# Coil_Switching_System.net
KiCad netlist of a schematic drawn in Altium Designer
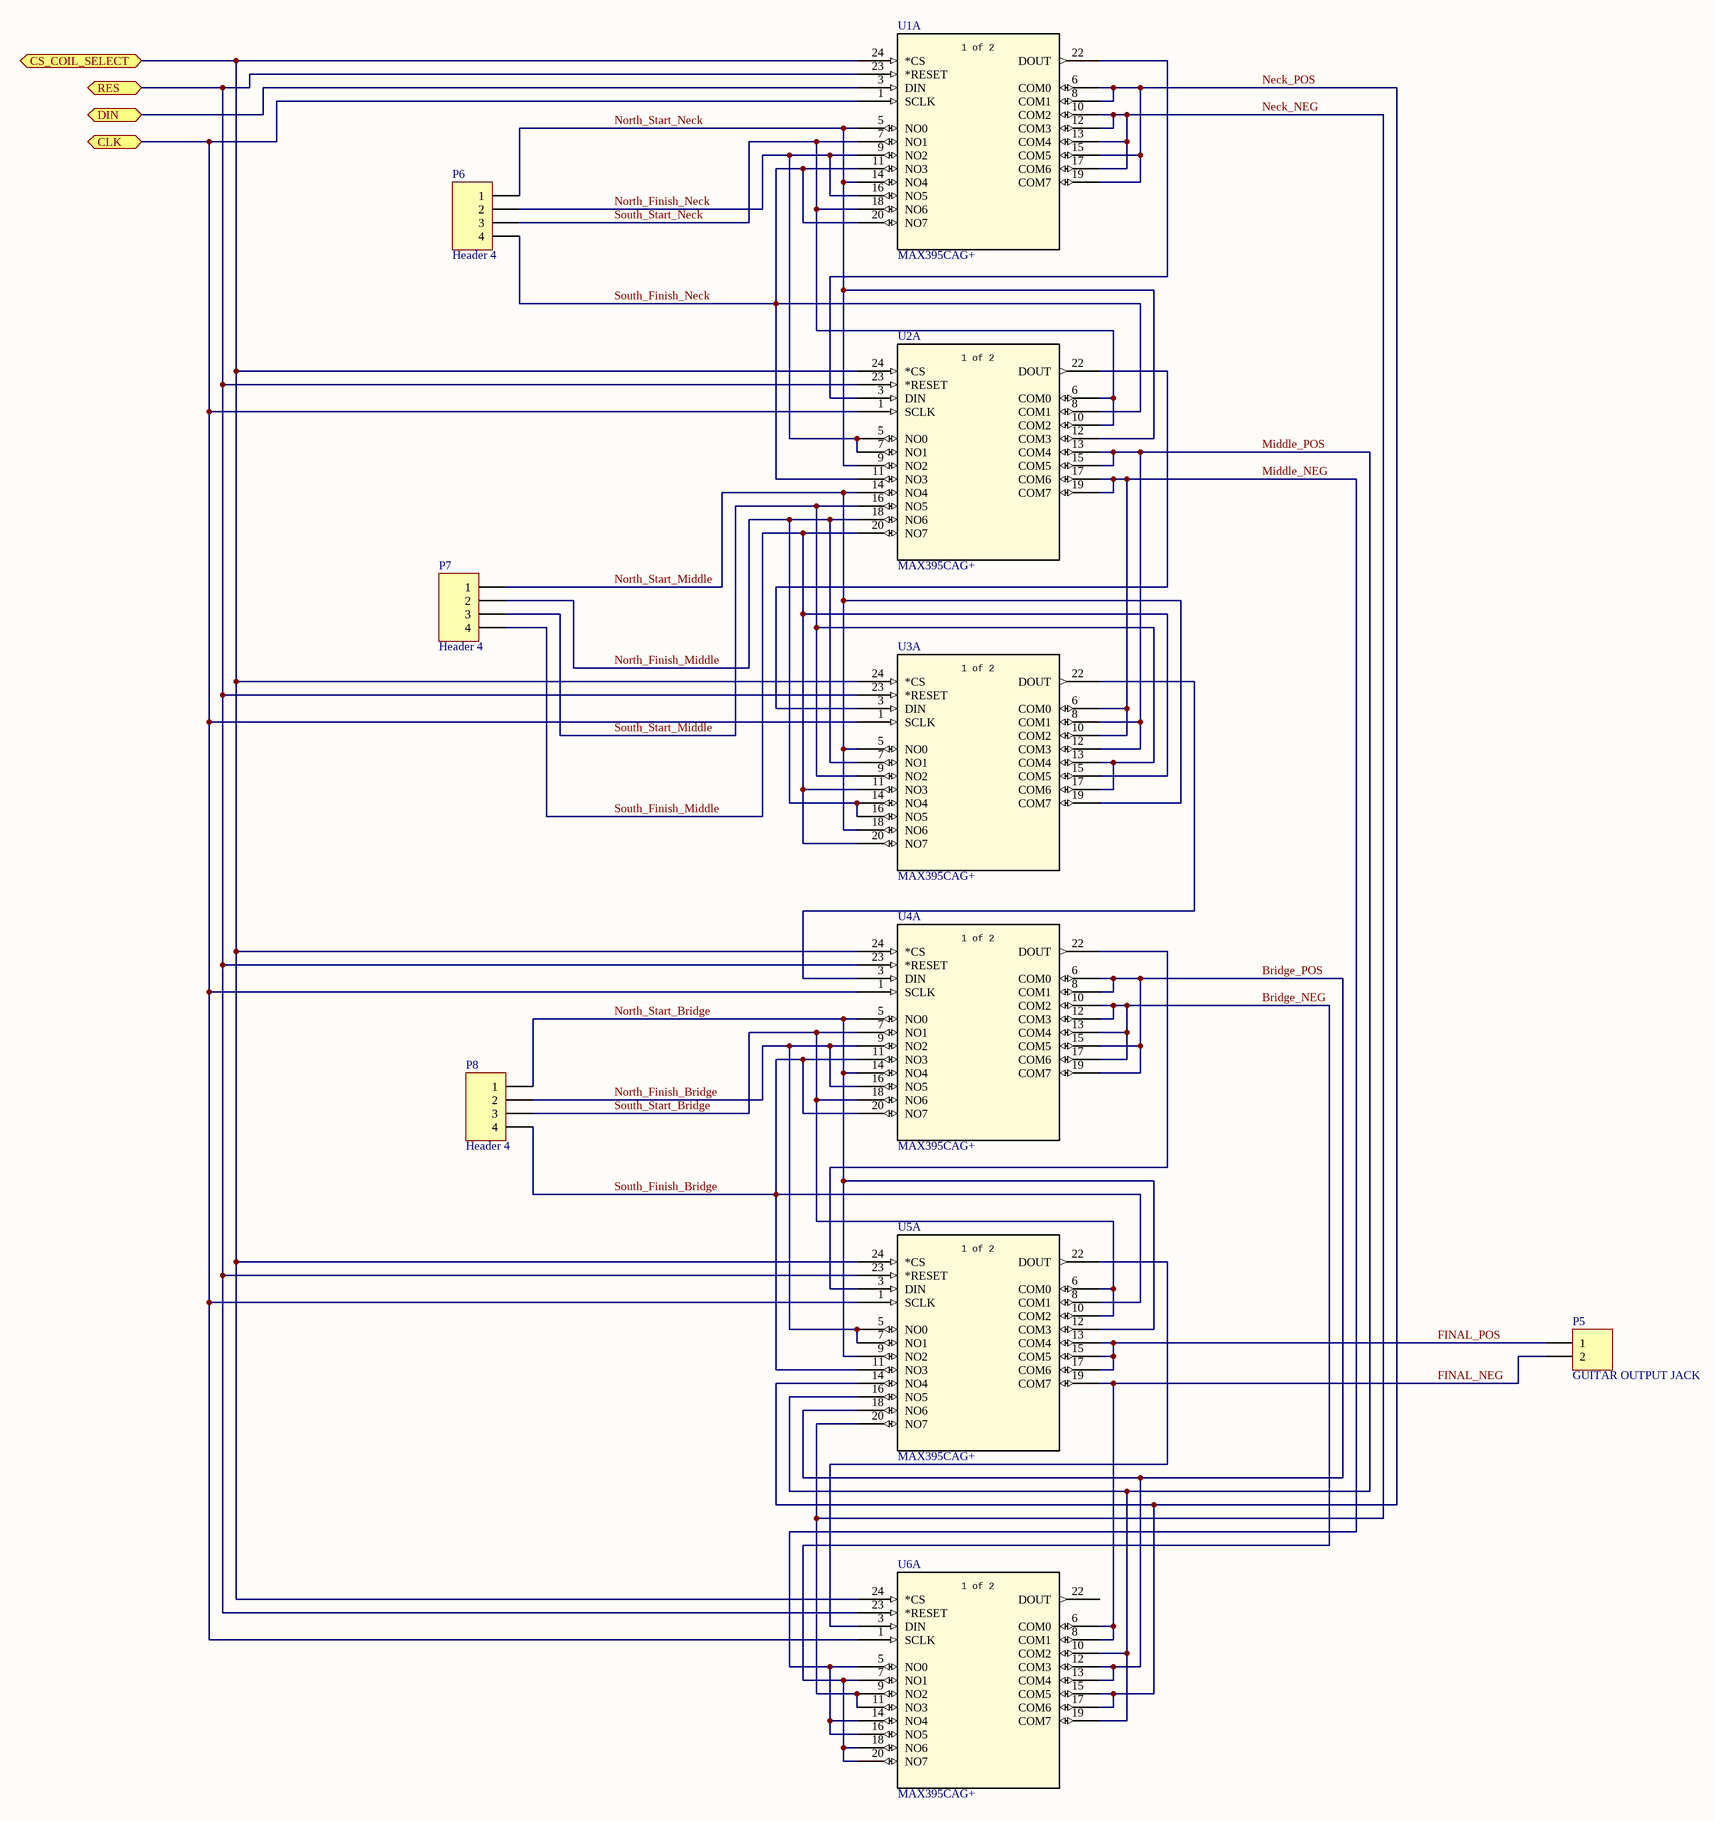
[diagram p0: Coil Switching System.SchDoc]

(export (version "E")
  (design (tool "Eeschema 10.0.6"))
  (components
    (comp (ref "P5")
      (value "GUITAR OUTPUT JACK")
      (footprint "HDR1X2")
      (description "Header, 2-Pin")
      (fields (field (name "PUBLISHER") "Altium Limited"))
      (libsource (lib "Miscellaneous Connectors") (part "Header 2"))
    )
    (comp (ref "P6")
      (value "Header 4")
      (footprint "HDR1X4")
      (description "Header, 4-Pin")
      (fields (field (name "PUBLISHER") "Altium Limited"))
      (libsource (lib "Miscellaneous Connectors") (part "Header 4"))
    )
    (comp (ref "P7")
      (value "Header 4")
      (footprint "HDR1X4")
      (description "Header, 4-Pin")
      (fields (field (name "PUBLISHER") "Altium Limited"))
      (libsource (lib "Miscellaneous Connectors") (part "Header 4"))
    )
    (comp (ref "P8")
      (value "Header 4")
      (footprint "HDR1X4")
      (description "Header, 4-Pin")
      (fields (field (name "PUBLISHER") "Altium Limited"))
      (libsource (lib "Miscellaneous Connectors") (part "Header 4"))
    )
    (comp (ref "U1")
      (value "MAX395CAG+")
      (footprint "21-0056C_24_MXM")
      (description "No Description Available")
      (fields (field (name "COPYRIGHT") "Copyright (C) 2018 Accelerated Designs. All rights reserved"))
      (libsource (lib "MAX395") (part "MAX395CAG+"))
    )
    (comp (ref "U2")
      (value "MAX395CAG+")
      (footprint "21-0056C_24_MXM")
      (description "No Description Available")
      (fields (field (name "COPYRIGHT") "Copyright (C) 2018 Accelerated Designs. All rights reserved"))
      (libsource (lib "MAX395") (part "MAX395CAG+"))
    )
    (comp (ref "U3")
      (value "MAX395CAG+")
      (footprint "21-0056C_24_MXM")
      (description "No Description Available")
      (fields (field (name "COPYRIGHT") "Copyright (C) 2018 Accelerated Designs. All rights reserved"))
      (libsource (lib "MAX395") (part "MAX395CAG+"))
    )
    (comp (ref "U4")
      (value "MAX395CAG+")
      (footprint "21-0056C_24_MXM")
      (description "No Description Available")
      (fields (field (name "COPYRIGHT") "Copyright (C) 2018 Accelerated Designs. All rights reserved"))
      (libsource (lib "MAX395") (part "MAX395CAG+"))
    )
    (comp (ref "U5")
      (value "MAX395CAG+")
      (footprint "21-0056C_24_MXM")
      (description "No Description Available")
      (fields (field (name "COPYRIGHT") "Copyright (C) 2018 Accelerated Designs. All rights reserved"))
      (libsource (lib "MAX395") (part "MAX395CAG+"))
    )
    (comp (ref "U6")
      (value "MAX395CAG+")
      (footprint "21-0056C_24_MXM")
      (description "No Description Available")
      (fields (field (name "COPYRIGHT") "Copyright (C) 2018 Accelerated Designs. All rights reserved"))
      (libsource (lib "MAX395") (part "MAX395CAG+"))
    )
  )
  (nets
    (net (code "1") (name "/Bridge_NEG") (class "Default")
      (node (ref "U4") (pin "10") (pinfunction "COM2_10") (pintype "bidirectional"))
      (node (ref "U4") (pin "12") (pinfunction "COM3_12") (pintype "bidirectional"))
      (node (ref "U4") (pin "13") (pinfunction "COM4_13") (pintype "bidirectional"))
      (node (ref "U4") (pin "17") (pinfunction "COM6_17") (pintype "bidirectional"))
      (node (ref "U6") (pin "18") (pinfunction "NO6_18") (pintype "bidirectional"))
      (node (ref "U6") (pin "20") (pinfunction "NO7_20") (pintype "bidirectional"))
      (node (ref "U6") (pin "7") (pinfunction "NO1_7") (pintype "bidirectional"))
    )
    (net (code "2") (name "/Bridge_POS") (class "Default")
      (node (ref "U4") (pin "15") (pinfunction "COM5_15") (pintype "bidirectional"))
      (node (ref "U4") (pin "19") (pinfunction "COM7_19") (pintype "bidirectional"))
      (node (ref "U4") (pin "6") (pinfunction "COM0_6") (pintype "bidirectional"))
      (node (ref "U4") (pin "8") (pinfunction "COM1_8") (pintype "bidirectional"))
      (node (ref "U5") (pin "18") (pinfunction "NO6_18") (pintype "bidirectional"))
      (node (ref "U6") (pin "12") (pinfunction "COM3_12") (pintype "bidirectional"))
      (node (ref "U6") (pin "13") (pinfunction "COM4_13") (pintype "bidirectional"))
    )
    (net (code "3") (name "/CLK") (class "Default")
      (node (ref "U1") (pin "1") (pinfunction "SCLK_1") (pintype "input"))
      (node (ref "U2") (pin "1") (pinfunction "SCLK_1") (pintype "input"))
      (node (ref "U3") (pin "1") (pinfunction "SCLK_1") (pintype "input"))
      (node (ref "U4") (pin "1") (pinfunction "SCLK_1") (pintype "input"))
      (node (ref "U5") (pin "1") (pinfunction "SCLK_1") (pintype "input"))
      (node (ref "U6") (pin "1") (pinfunction "SCLK_1") (pintype "input"))
    )
    (net (code "4") (name "/CS_COIL_SELECT") (class "Default")
      (node (ref "U1") (pin "24") (pinfunction "*CS_24") (pintype "input"))
      (node (ref "U2") (pin "24") (pinfunction "*CS_24") (pintype "input"))
      (node (ref "U3") (pin "24") (pinfunction "*CS_24") (pintype "input"))
      (node (ref "U4") (pin "24") (pinfunction "*CS_24") (pintype "input"))
      (node (ref "U5") (pin "24") (pinfunction "*CS_24") (pintype "input"))
      (node (ref "U6") (pin "24") (pinfunction "*CS_24") (pintype "input"))
    )
    (net (code "5") (name "/DIN") (class "Default")
      (node (ref "U1") (pin "3") (pinfunction "DIN_3") (pintype "input"))
    )
    (net (code "6") (name "/FINAL_NEG") (class "Default")
      (node (ref "P5") (pin "2") (pinfunction "2_2") (pintype "passive"))
      (node (ref "U5") (pin "19") (pinfunction "COM7_19") (pintype "bidirectional"))
      (node (ref "U6") (pin "6") (pinfunction "COM0_6") (pintype "bidirectional"))
      (node (ref "U6") (pin "8") (pinfunction "COM1_8") (pintype "bidirectional"))
    )
    (net (code "7") (name "/FINAL_POS") (class "Default")
      (node (ref "P5") (pin "1") (pinfunction "1_1") (pintype "passive"))
      (node (ref "U5") (pin "13") (pinfunction "COM4_13") (pintype "bidirectional"))
      (node (ref "U5") (pin "15") (pinfunction "COM5_15") (pintype "bidirectional"))
      (node (ref "U5") (pin "17") (pinfunction "COM6_17") (pintype "bidirectional"))
    )
    (net (code "8") (name "/Middle_NEG") (class "Default")
      (node (ref "U2") (pin "17") (pinfunction "COM6_17") (pintype "bidirectional"))
      (node (ref "U2") (pin "19") (pinfunction "COM7_19") (pintype "bidirectional"))
      (node (ref "U3") (pin "10") (pinfunction "COM2_10") (pintype "bidirectional"))
      (node (ref "U3") (pin "6") (pinfunction "COM0_6") (pintype "bidirectional"))
      (node (ref "U6") (pin "14") (pinfunction "NO4_14") (pintype "bidirectional"))
      (node (ref "U6") (pin "16") (pinfunction "NO5_16") (pintype "bidirectional"))
      (node (ref "U6") (pin "5") (pinfunction "NO0_5") (pintype "bidirectional"))
    )
    (net (code "9") (name "/Middle_POS") (class "Default")
      (node (ref "U2") (pin "13") (pinfunction "COM4_13") (pintype "bidirectional"))
      (node (ref "U2") (pin "15") (pinfunction "COM5_15") (pintype "bidirectional"))
      (node (ref "U3") (pin "12") (pinfunction "COM3_12") (pintype "bidirectional"))
      (node (ref "U3") (pin "8") (pinfunction "COM1_8") (pintype "bidirectional"))
      (node (ref "U5") (pin "16") (pinfunction "NO5_16") (pintype "bidirectional"))
      (node (ref "U6") (pin "10") (pinfunction "COM2_10") (pintype "bidirectional"))
      (node (ref "U6") (pin "19") (pinfunction "COM7_19") (pintype "bidirectional"))
    )
    (net (code "10") (name "/Neck_NEG") (class "Default")
      (node (ref "U1") (pin "10") (pinfunction "COM2_10") (pintype "bidirectional"))
      (node (ref "U1") (pin "12") (pinfunction "COM3_12") (pintype "bidirectional"))
      (node (ref "U1") (pin "13") (pinfunction "COM4_13") (pintype "bidirectional"))
      (node (ref "U1") (pin "17") (pinfunction "COM6_17") (pintype "bidirectional"))
      (node (ref "U5") (pin "20") (pinfunction "NO7_20") (pintype "bidirectional"))
      (node (ref "U6") (pin "11") (pinfunction "NO3_11") (pintype "bidirectional"))
      (node (ref "U6") (pin "9") (pinfunction "NO2_9") (pintype "bidirectional"))
    )
    (net (code "11") (name "/Neck_POS") (class "Default")
      (node (ref "U1") (pin "15") (pinfunction "COM5_15") (pintype "bidirectional"))
      (node (ref "U1") (pin "19") (pinfunction "COM7_19") (pintype "bidirectional"))
      (node (ref "U1") (pin "6") (pinfunction "COM0_6") (pintype "bidirectional"))
      (node (ref "U1") (pin "8") (pinfunction "COM1_8") (pintype "bidirectional"))
      (node (ref "U5") (pin "14") (pinfunction "NO4_14") (pintype "bidirectional"))
      (node (ref "U6") (pin "15") (pinfunction "COM5_15") (pintype "bidirectional"))
      (node (ref "U6") (pin "17") (pinfunction "COM6_17") (pintype "bidirectional"))
    )
    (net (code "12") (name "/North_Finish_Bridge") (class "Default")
      (node (ref "P8") (pin "2") (pinfunction "2_2") (pintype "passive"))
      (node (ref "U4") (pin "16") (pinfunction "NO5_16") (pintype "bidirectional"))
      (node (ref "U4") (pin "9") (pinfunction "NO2_9") (pintype "bidirectional"))
      (node (ref "U5") (pin "5") (pinfunction "NO0_5") (pintype "bidirectional"))
      (node (ref "U5") (pin "7") (pinfunction "NO1_7") (pintype "bidirectional"))
    )
    (net (code "13") (name "/North_Finish_Middle") (class "Default")
      (node (ref "P7") (pin "2") (pinfunction "2_2") (pintype "passive"))
      (node (ref "U2") (pin "18") (pinfunction "NO6_18") (pintype "bidirectional"))
      (node (ref "U3") (pin "14") (pinfunction "NO4_14") (pintype "bidirectional"))
      (node (ref "U3") (pin "16") (pinfunction "NO5_16") (pintype "bidirectional"))
      (node (ref "U3") (pin "7") (pinfunction "NO1_7") (pintype "bidirectional"))
    )
    (net (code "14") (name "/North_Finish_Neck") (class "Default")
      (node (ref "P6") (pin "2") (pinfunction "2_2") (pintype "passive"))
      (node (ref "U1") (pin "16") (pinfunction "NO5_16") (pintype "bidirectional"))
      (node (ref "U1") (pin "9") (pinfunction "NO2_9") (pintype "bidirectional"))
      (node (ref "U2") (pin "5") (pinfunction "NO0_5") (pintype "bidirectional"))
      (node (ref "U2") (pin "7") (pinfunction "NO1_7") (pintype "bidirectional"))
    )
    (net (code "15") (name "/North_Start_Bridge") (class "Default")
      (node (ref "P8") (pin "1") (pinfunction "1_1") (pintype "passive"))
      (node (ref "U4") (pin "14") (pinfunction "NO4_14") (pintype "bidirectional"))
      (node (ref "U4") (pin "5") (pinfunction "NO0_5") (pintype "bidirectional"))
      (node (ref "U5") (pin "12") (pinfunction "COM3_12") (pintype "bidirectional"))
      (node (ref "U5") (pin "9") (pinfunction "NO2_9") (pintype "bidirectional"))
    )
    (net (code "16") (name "/North_Start_Middle") (class "Default")
      (node (ref "P7") (pin "1") (pinfunction "1_1") (pintype "passive"))
      (node (ref "U2") (pin "14") (pinfunction "NO4_14") (pintype "bidirectional"))
      (node (ref "U3") (pin "18") (pinfunction "NO6_18") (pintype "bidirectional"))
      (node (ref "U3") (pin "19") (pinfunction "COM7_19") (pintype "bidirectional"))
      (node (ref "U3") (pin "5") (pinfunction "NO0_5") (pintype "bidirectional"))
    )
    (net (code "17") (name "/North_Start_Neck") (class "Default")
      (node (ref "P6") (pin "1") (pinfunction "1_1") (pintype "passive"))
      (node (ref "U1") (pin "14") (pinfunction "NO4_14") (pintype "bidirectional"))
      (node (ref "U1") (pin "5") (pinfunction "NO0_5") (pintype "bidirectional"))
      (node (ref "U2") (pin "12") (pinfunction "COM3_12") (pintype "bidirectional"))
      (node (ref "U2") (pin "9") (pinfunction "NO2_9") (pintype "bidirectional"))
    )
    (net (code "18") (name "/RES") (class "Default")
      (node (ref "U1") (pin "23") (pinfunction "*RESET_23") (pintype "input"))
      (node (ref "U2") (pin "23") (pinfunction "*RESET_23") (pintype "input"))
      (node (ref "U3") (pin "23") (pinfunction "*RESET_23") (pintype "input"))
      (node (ref "U4") (pin "23") (pinfunction "*RESET_23") (pintype "input"))
      (node (ref "U5") (pin "23") (pinfunction "*RESET_23") (pintype "input"))
      (node (ref "U6") (pin "23") (pinfunction "*RESET_23") (pintype "input"))
    )
    (net (code "19") (name "/South_Finish_Bridge") (class "Default")
      (node (ref "P8") (pin "4") (pinfunction "4_4") (pintype "passive"))
      (node (ref "U4") (pin "11") (pinfunction "NO3_11") (pintype "bidirectional"))
      (node (ref "U4") (pin "20") (pinfunction "NO7_20") (pintype "bidirectional"))
      (node (ref "U5") (pin "11") (pinfunction "NO3_11") (pintype "bidirectional"))
      (node (ref "U5") (pin "8") (pinfunction "COM1_8") (pintype "bidirectional"))
    )
    (net (code "20") (name "/South_Finish_Middle") (class "Default")
      (node (ref "P7") (pin "4") (pinfunction "4_4") (pintype "passive"))
      (node (ref "U2") (pin "20") (pinfunction "NO7_20") (pintype "bidirectional"))
      (node (ref "U3") (pin "11") (pinfunction "NO3_11") (pintype "bidirectional"))
      (node (ref "U3") (pin "15") (pinfunction "COM5_15") (pintype "bidirectional"))
      (node (ref "U3") (pin "20") (pinfunction "NO7_20") (pintype "bidirectional"))
    )
    (net (code "21") (name "/South_Finish_Neck") (class "Default")
      (node (ref "P6") (pin "4") (pinfunction "4_4") (pintype "passive"))
      (node (ref "U1") (pin "11") (pinfunction "NO3_11") (pintype "bidirectional"))
      (node (ref "U1") (pin "20") (pinfunction "NO7_20") (pintype "bidirectional"))
      (node (ref "U2") (pin "11") (pinfunction "NO3_11") (pintype "bidirectional"))
      (node (ref "U2") (pin "8") (pinfunction "COM1_8") (pintype "bidirectional"))
    )
    (net (code "22") (name "/South_Start_Bridge") (class "Default")
      (node (ref "P8") (pin "3") (pinfunction "3_3") (pintype "passive"))
      (node (ref "U4") (pin "18") (pinfunction "NO6_18") (pintype "bidirectional"))
      (node (ref "U4") (pin "7") (pinfunction "NO1_7") (pintype "bidirectional"))
      (node (ref "U5") (pin "10") (pinfunction "COM2_10") (pintype "bidirectional"))
      (node (ref "U5") (pin "6") (pinfunction "COM0_6") (pintype "bidirectional"))
    )
    (net (code "23") (name "/South_Start_Middle") (class "Default")
      (node (ref "P7") (pin "3") (pinfunction "3_3") (pintype "passive"))
      (node (ref "U2") (pin "16") (pinfunction "NO5_16") (pintype "bidirectional"))
      (node (ref "U3") (pin "13") (pinfunction "COM4_13") (pintype "bidirectional"))
      (node (ref "U3") (pin "17") (pinfunction "COM6_17") (pintype "bidirectional"))
      (node (ref "U3") (pin "9") (pinfunction "NO2_9") (pintype "bidirectional"))
    )
    (net (code "24") (name "/South_Start_Neck") (class "Default")
      (node (ref "P6") (pin "3") (pinfunction "3_3") (pintype "passive"))
      (node (ref "U1") (pin "18") (pinfunction "NO6_18") (pintype "bidirectional"))
      (node (ref "U1") (pin "7") (pinfunction "NO1_7") (pintype "bidirectional"))
      (node (ref "U2") (pin "10") (pinfunction "COM2_10") (pintype "bidirectional"))
      (node (ref "U2") (pin "6") (pinfunction "COM0_6") (pintype "bidirectional"))
    )
    (net (code "25") (name "Net-(U1A-DOUT)") (class "Default")
      (node (ref "U1") (pin "22") (pinfunction "DOUT_22") (pintype "output"))
      (node (ref "U2") (pin "3") (pinfunction "DIN_3") (pintype "input"))
    )
    (net (code "26") (name "Net-(U2A-DOUT)") (class "Default")
      (node (ref "U2") (pin "22") (pinfunction "DOUT_22") (pintype "output"))
      (node (ref "U3") (pin "3") (pinfunction "DIN_3") (pintype "input"))
    )
    (net (code "27") (name "Net-(U3A-DOUT)") (class "Default")
      (node (ref "U3") (pin "22") (pinfunction "DOUT_22") (pintype "output"))
      (node (ref "U4") (pin "3") (pinfunction "DIN_3") (pintype "input"))
    )
    (net (code "28") (name "Net-(U4A-DOUT)") (class "Default")
      (node (ref "U4") (pin "22") (pinfunction "DOUT_22") (pintype "output"))
      (node (ref "U5") (pin "3") (pinfunction "DIN_3") (pintype "input"))
    )
    (net (code "29") (name "Net-(U5A-DOUT)") (class "Default")
      (node (ref "U5") (pin "22") (pinfunction "DOUT_22") (pintype "output"))
      (node (ref "U6") (pin "3") (pinfunction "DIN_3") (pintype "input"))
    )
    (net (code "30") (name "unconnected-(U6A-DOUT-Pad22)") (class "Default")
      (node (ref "U6") (pin "22") (pinfunction "DOUT_22") (pintype "output"))
    )
  )
)
